# CamLanternBRD.net
KiCad netlist of a schematic drawn in EAGLE
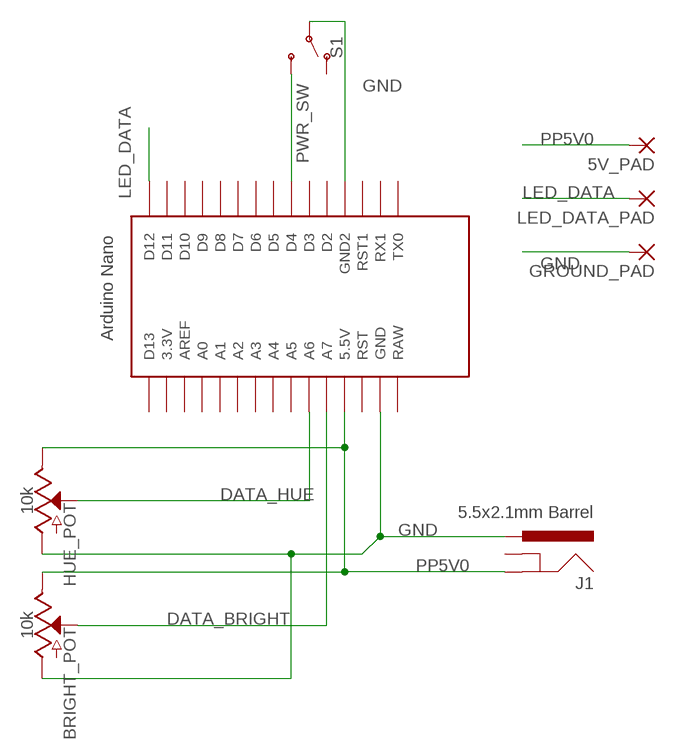
[diagram p0: schematic, sheet 1]

(export (version "E")
  (design (tool "Eeschema 10.0.6"))
  (components
    (comp (ref "5V_PAD")
      (value "1,6/0,9")
      (footprint "eagle-import:1,6_0,9")
      (libsource (lib "eagle-import") (part "1,6/0,9"))
    )
    (comp (ref "BRIGHT_POT")
      (value "10k")
      (footprint "eagle-import:POT-PTH-ALPS-KIT")
      (libsource (lib "eagle-import") (part "POTENTIOMETER-PTH-9MM-1/20W-20%-KIT"))
    )
    (comp (ref "GROUND_PAD")
      (value "1,6/0,9")
      (footprint "eagle-import:1,6_0,9")
      (libsource (lib "eagle-import") (part "1,6/0,9"))
    )
    (comp (ref "HUE_POT")
      (value "10k")
      (footprint "eagle-import:POT-PTH-ALPS-KIT")
      (libsource (lib "eagle-import") (part "POTENTIOMETER-PTH-9MM-1/20W-20%-KIT"))
    )
    (comp (ref "J1")
      (value "5.5x2.1mm Barrel")
      (footprint "eagle-import:POWER_JACK_SMD")
      (libsource (lib "eagle-import") (part "POWER_JACKSMD"))
    )
    (comp (ref "LED_DATA_PAD")
      (value "1,6/0,9")
      (footprint "eagle-import:1,6_0,9")
      (libsource (lib "eagle-import") (part "1,6/0,9"))
    )
    (comp (ref "S1")
      (value "SWITCH-SPDT-PTH-11.6X4.0MM")
      (footprint "eagle-import:SWITCH_SPDT_PTH_11.6X4.0MM")
      (libsource (lib "eagle-import") (part "SWITCH-SPDT-PTH-11.6X4.0MM"))
    )
    (comp (ref "U$2")
      (value "NANO")
      (footprint "eagle-import:NANO")
      (libsource (lib "eagle-import") (part "NANO"))
    )
  )
  (nets
    (net (code "1") (name "/DATA_BRIGHT") (class "Default")
      (node (ref "BRIGHT_POT") (pin "P$2") (pinfunction "S_P$2") (pintype "passive"))
      (node (ref "U$2") (pin "A7") (pinfunction "A7_A7") (pintype "bidirectional"))
    )
    (net (code "2") (name "/DATA_HUE") (class "Default")
      (node (ref "HUE_POT") (pin "P$2") (pinfunction "S_P$2") (pintype "passive"))
      (node (ref "U$2") (pin "A6") (pinfunction "A6_A6") (pintype "bidirectional"))
    )
    (net (code "3") (name "/GND") (class "Default")
      (node (ref "BRIGHT_POT") (pin "P$3") (pinfunction "A_P$3") (pintype "passive"))
      (node (ref "GROUND_PAD") (pin "1") (pinfunction "P_1") (pintype "passive"))
      (node (ref "HUE_POT") (pin "P$3") (pinfunction "A_P$3") (pintype "passive"))
      (node (ref "J1") (pin "VIN0") (pinfunction "PWR_VIN0") (pintype "bidirectional"))
      (node (ref "S1") (pin "2") (pinfunction "P_2") (pintype "passive"))
      (node (ref "U$2") (pin "GND") (pinfunction "GND_GND") (pintype "bidirectional"))
      (node (ref "U$2") (pin "GND1") (pinfunction "GND2_GND1") (pintype "bidirectional"))
    )
    (net (code "4") (name "/LED_DATA") (class "Default")
      (node (ref "LED_DATA_PAD") (pin "1") (pinfunction "P_1") (pintype "passive"))
      (node (ref "U$2") (pin "D12") (pinfunction "D12_D12") (pintype "bidirectional"))
    )
    (net (code "5") (name "/PP5V0") (class "Default")
      (node (ref "5V_PAD") (pin "1") (pinfunction "P_1") (pintype "passive"))
      (node (ref "BRIGHT_POT") (pin "P$1") (pinfunction "E_P$1") (pintype "passive"))
      (node (ref "HUE_POT") (pin "P$1") (pinfunction "E_P$1") (pintype "passive"))
      (node (ref "J1") (pin "P$4") (pinfunction "GND_P$4") (pintype "bidirectional"))
      (node (ref "U$2") (pin "5V") (pinfunction "5.5V_5V") (pintype "bidirectional"))
    )
    (net (code "6") (name "/PWR_SW") (class "Default")
      (node (ref "S1") (pin "3") (pinfunction "S_3") (pintype "passive"))
      (node (ref "U$2") (pin "D4") (pinfunction "D4_D4") (pintype "bidirectional"))
    )
    (net (code "7") (name "unconnected-(J1-GNDBREAK-PadGND)") (class "Default")
      (node (ref "J1") (pin "GND") (pinfunction "GNDBREAK_GND") (pintype "bidirectional"))
    )
    (net (code "8") (name "unconnected-(S1-O-Pad1)") (class "Default")
      (node (ref "S1") (pin "1") (pinfunction "O_1") (pintype "passive"))
    )
    (net (code "9") (name "unconnected-(U$2-Pad3.3V)") (class "Default")
      (node (ref "U$2") (pin "3.3V") (pinfunction "3.3V_3.3V") (pintype "bidirectional"))
    )
    (net (code "10") (name "unconnected-(U$2-PadA0)") (class "Default")
      (node (ref "U$2") (pin "A0") (pinfunction "A0_A0") (pintype "bidirectional"))
    )
    (net (code "11") (name "unconnected-(U$2-PadA1)") (class "Default")
      (node (ref "U$2") (pin "A1") (pinfunction "A1_A1") (pintype "bidirectional"))
    )
    (net (code "12") (name "unconnected-(U$2-PadA2)") (class "Default")
      (node (ref "U$2") (pin "A2") (pinfunction "A2_A2") (pintype "bidirectional"))
    )
    (net (code "13") (name "unconnected-(U$2-PadA3)") (class "Default")
      (node (ref "U$2") (pin "A3") (pinfunction "A3_A3") (pintype "bidirectional"))
    )
    (net (code "14") (name "unconnected-(U$2-PadA4)") (class "Default")
      (node (ref "U$2") (pin "A4") (pinfunction "A4_A4") (pintype "bidirectional"))
    )
    (net (code "15") (name "unconnected-(U$2-PadA5)") (class "Default")
      (node (ref "U$2") (pin "A5") (pinfunction "A5_A5") (pintype "bidirectional"))
    )
    (net (code "16") (name "unconnected-(U$2-PadAREF)") (class "Default")
      (node (ref "U$2") (pin "AREF") (pinfunction "AREF_AREF") (pintype "bidirectional"))
    )
    (net (code "17") (name "unconnected-(U$2-PadD2)") (class "Default")
      (node (ref "U$2") (pin "D2") (pinfunction "D2_D2") (pintype "bidirectional"))
    )
    (net (code "18") (name "unconnected-(U$2-PadD3)") (class "Default")
      (node (ref "U$2") (pin "D3") (pinfunction "D3_D3") (pintype "bidirectional"))
    )
    (net (code "19") (name "unconnected-(U$2-PadD5)") (class "Default")
      (node (ref "U$2") (pin "D5") (pinfunction "D5_D5") (pintype "bidirectional"))
    )
    (net (code "20") (name "unconnected-(U$2-PadD6)") (class "Default")
      (node (ref "U$2") (pin "D6") (pinfunction "D6_D6") (pintype "bidirectional"))
    )
    (net (code "21") (name "unconnected-(U$2-PadD7)") (class "Default")
      (node (ref "U$2") (pin "D7") (pinfunction "D7_D7") (pintype "bidirectional"))
    )
    (net (code "22") (name "unconnected-(U$2-PadD8)") (class "Default")
      (node (ref "U$2") (pin "D8") (pinfunction "D8_D8") (pintype "bidirectional"))
    )
    (net (code "23") (name "unconnected-(U$2-PadD9)") (class "Default")
      (node (ref "U$2") (pin "D9") (pinfunction "D9_D9") (pintype "bidirectional"))
    )
    (net (code "24") (name "unconnected-(U$2-PadD10)") (class "Default")
      (node (ref "U$2") (pin "D10") (pinfunction "D10_D10") (pintype "bidirectional"))
    )
    (net (code "25") (name "unconnected-(U$2-PadD11)") (class "Default")
      (node (ref "U$2") (pin "D11") (pinfunction "D11_D11") (pintype "bidirectional"))
    )
    (net (code "26") (name "unconnected-(U$2-PadD13)") (class "Default")
      (node (ref "U$2") (pin "D13") (pinfunction "D13_D13") (pintype "bidirectional"))
    )
    (net (code "27") (name "unconnected-(U$2-PadICSP1)") (class "Default")
      (node (ref "U$2") (pin "ICSP1") (pinfunction "ICSP1_ICSP1") (pintype "bidirectional"))
    )
    (net (code "28") (name "unconnected-(U$2-PadICSP2)") (class "Default")
      (node (ref "U$2") (pin "ICSP2") (pinfunction "ICSP2_ICSP2") (pintype "bidirectional"))
    )
    (net (code "29") (name "unconnected-(U$2-PadICSP3)") (class "Default")
      (node (ref "U$2") (pin "ICSP3") (pinfunction "ICSP3_ICSP3") (pintype "bidirectional"))
    )
    (net (code "30") (name "unconnected-(U$2-PadICSP4)") (class "Default")
      (node (ref "U$2") (pin "ICSP4") (pinfunction "ICSP4_ICSP4") (pintype "bidirectional"))
    )
    (net (code "31") (name "unconnected-(U$2-PadICSP5)") (class "Default")
      (node (ref "U$2") (pin "ICSP5") (pinfunction "ICSP5_ICSP5") (pintype "bidirectional"))
    )
    (net (code "32") (name "unconnected-(U$2-PadICSP6)") (class "Default")
      (node (ref "U$2") (pin "ICSP6") (pinfunction "ICSP6_ICSP6") (pintype "bidirectional"))
    )
    (net (code "33") (name "unconnected-(U$2-PadRAW)") (class "Default")
      (node (ref "U$2") (pin "RAW") (pinfunction "RAW_RAW") (pintype "bidirectional"))
    )
    (net (code "34") (name "unconnected-(U$2-PadRST)") (class "Default")
      (node (ref "U$2") (pin "RST") (pinfunction "RST_RST") (pintype "bidirectional"))
    )
    (net (code "35") (name "unconnected-(U$2-PadRST1)") (class "Default")
      (node (ref "U$2") (pin "RST1") (pinfunction "RST1_RST1") (pintype "bidirectional"))
    )
    (net (code "36") (name "unconnected-(U$2-PadRX1)") (class "Default")
      (node (ref "U$2") (pin "RX1") (pinfunction "RX1_RX1") (pintype "bidirectional"))
    )
    (net (code "37") (name "unconnected-(U$2-PadTX0)") (class "Default")
      (node (ref "U$2") (pin "TX0") (pinfunction "TX0_TX0") (pintype "bidirectional"))
    )
  )
)
